# LoRa_Mini_Dev_v1_1.net
KiCad netlist of a schematic drawn in EAGLE
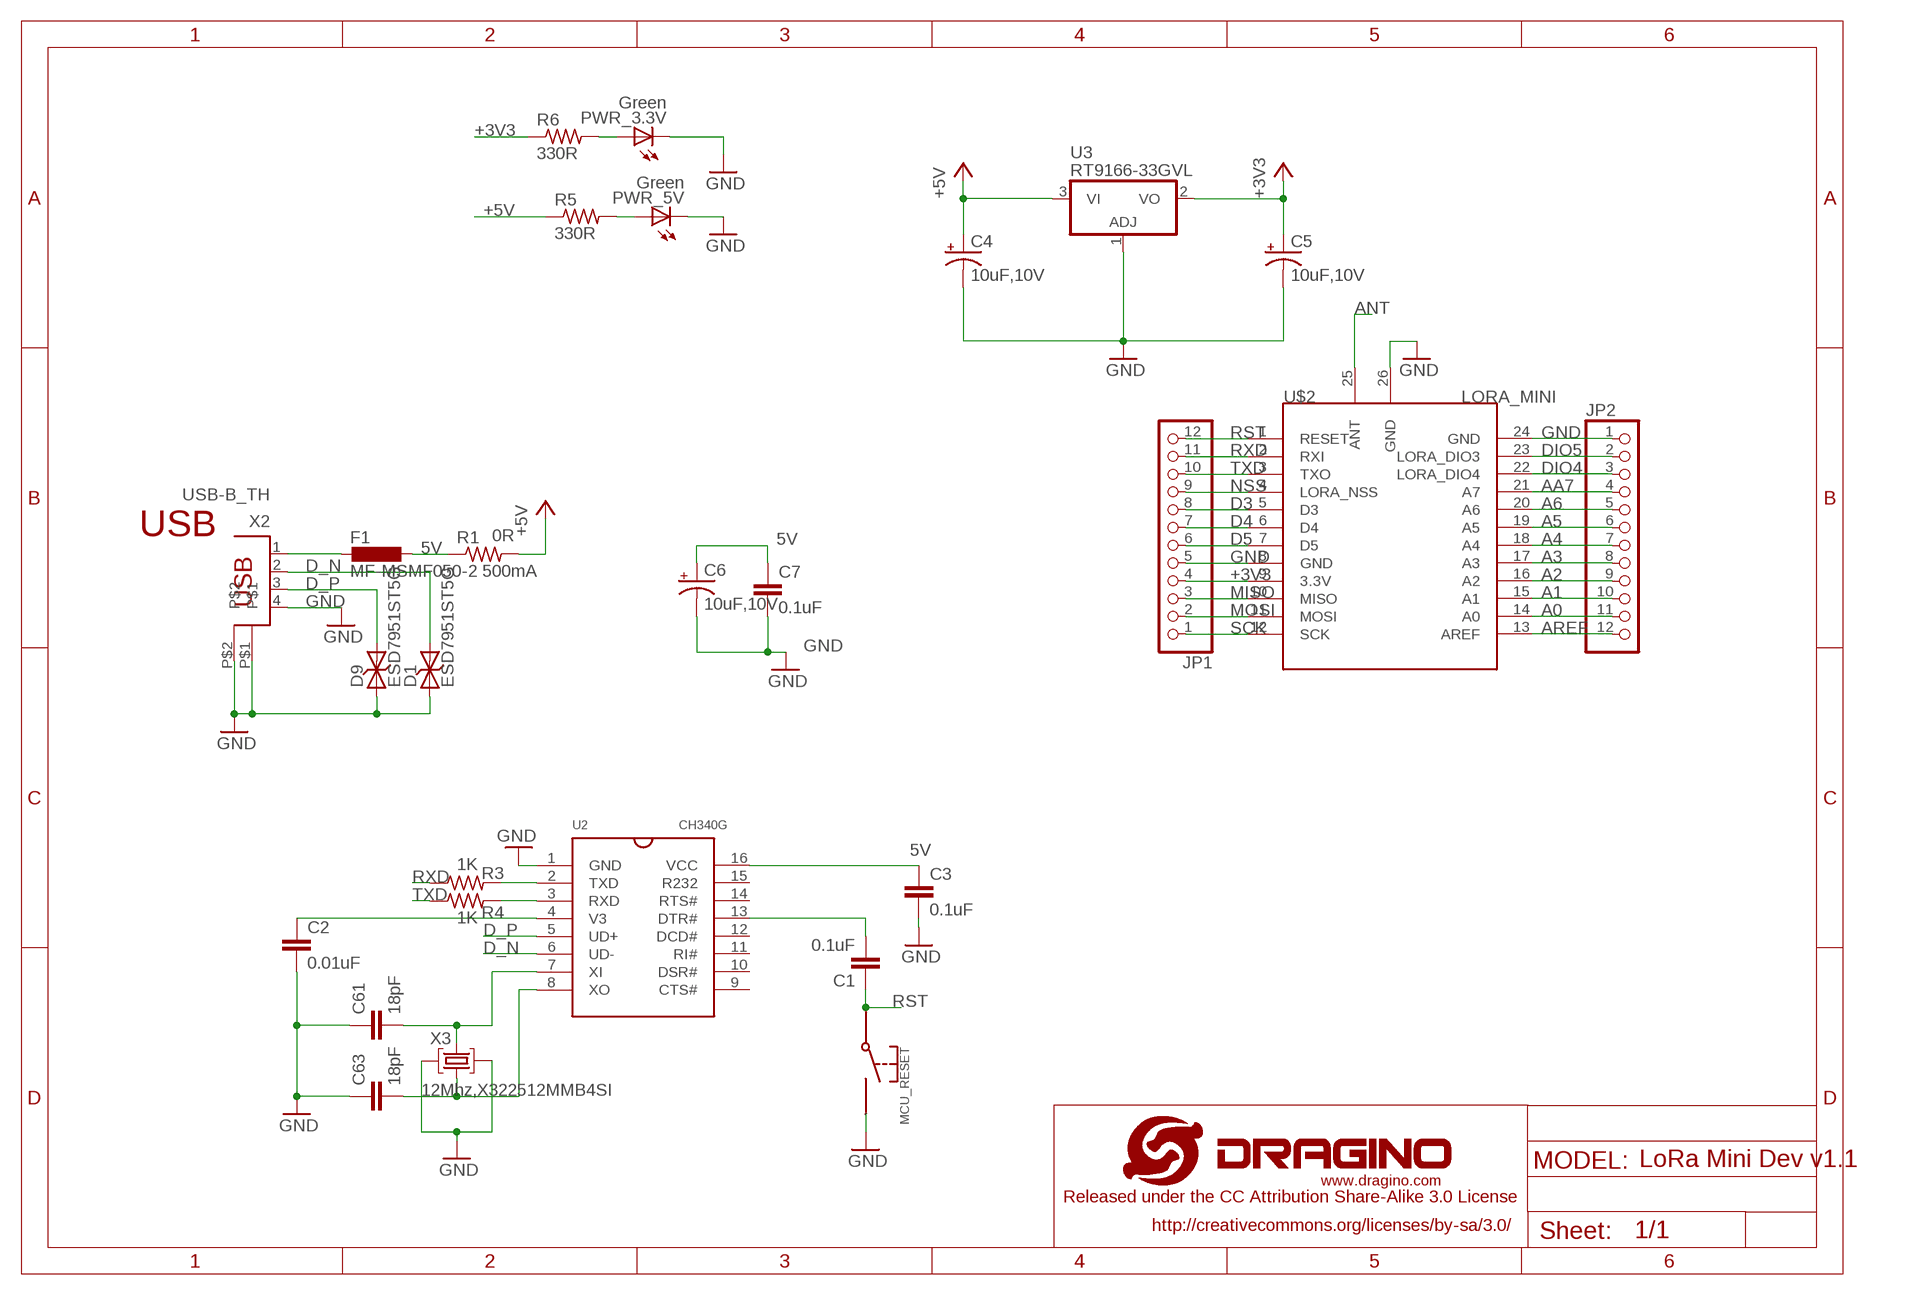
[diagram p0: schematic, sheet 1]

(export (version "E")
  (design (tool "Eeschema 10.0.6"))
  (components
    (comp (ref "C1")
      (value "0.1uF")
      (footprint "eagle-import:C0402")
      (libsource (lib "eagle-import") (part "C-EUC0402"))
    )
    (comp (ref "C2")
      (value "0.01uF")
      (footprint "eagle-import:C0402")
      (libsource (lib "eagle-import") (part "C-EUC0402"))
    )
    (comp (ref "C3")
      (value "0.1uF")
      (footprint "eagle-import:C0402")
      (libsource (lib "eagle-import") (part "C-EUC0402"))
    )
    (comp (ref "C4")
      (value "10uF,10V")
      (footprint "eagle-import:SMC_A")
      (libsource (lib "eagle-import") (part "CPOL-USSMCA"))
    )
    (comp (ref "C5")
      (value "10uF,10V")
      (footprint "eagle-import:SMC_A")
      (libsource (lib "eagle-import") (part "CPOL-USSMCA"))
    )
    (comp (ref "C6")
      (value "10uF,10V")
      (footprint "eagle-import:SMC_A")
      (libsource (lib "eagle-import") (part "CPOL-USSMCA"))
    )
    (comp (ref "C7")
      (value "0.1uF")
      (footprint "eagle-import:C0402")
      (libsource (lib "eagle-import") (part "C-EUC0402"))
    )
    (comp (ref "C61")
      (value "18pF")
      (footprint "eagle-import:C0402")
      (libsource (lib "eagle-import") (part "C-EUC0402"))
    )
    (comp (ref "C63")
      (value "18pF")
      (footprint "eagle-import:C0402")
      (libsource (lib "eagle-import") (part "C-EUC0402"))
    )
    (comp (ref "D1")
      (value "ESD7951ST5G")
      (footprint "eagle-import:SOD−923")
      (libsource (lib "eagle-import") (part "TVSSOD−923"))
    )
    (comp (ref "D9")
      (value "ESD7951ST5G")
      (footprint "eagle-import:SOD−923")
      (libsource (lib "eagle-import") (part "TVSSOD−923"))
    )
    (comp (ref "F1")
      (value "MF-MSMF050-2 500mA")
      (footprint "eagle-import:L1812")
      (libsource (lib "eagle-import") (part "L-EUL1812"))
    )
    (comp (ref "JP1")
      (value "PINHD-1X12")
      (footprint "eagle-import:1X12")
      (libsource (lib "eagle-import") (part "PINHD-1X12"))
    )
    (comp (ref "JP2")
      (value "PINHD-1X12")
      (footprint "eagle-import:1X12")
      (libsource (lib "eagle-import") (part "PINHD-1X12"))
    )
    (comp (ref "MCU_RESET")
      (value "SWITCH")
      (footprint "eagle-import:SWITCH_3X6X5MM")
      (libsource (lib "eagle-import") (part "SWITCH"))
    )
    (comp (ref "PWR_3.3V")
      (value "Green")
      (footprint "eagle-import:DRAGINO_CHIPLED_0603")
      (libsource (lib "eagle-import") (part "DRAGINO_LEDCHIPLED_0603"))
    )
    (comp (ref "PWR_5V")
      (value "Green")
      (footprint "eagle-import:DRAGINO_CHIPLED_0603")
      (libsource (lib "eagle-import") (part "DRAGINO_LEDCHIPLED_0603"))
    )
    (comp (ref "R1")
      (value "0R")
      (footprint "eagle-import:M0805")
      (libsource (lib "eagle-import") (part "R-US_M0805"))
    )
    (comp (ref "R3")
      (value "1K")
      (footprint "eagle-import:R0402")
      (libsource (lib "eagle-import") (part "R-US_R0402"))
    )
    (comp (ref "R4")
      (value "1K")
      (footprint "eagle-import:R0402")
      (libsource (lib "eagle-import") (part "R-US_R0402"))
    )
    (comp (ref "R5")
      (value "330R")
      (footprint "eagle-import:R0402")
      (libsource (lib "eagle-import") (part "R-US_R0402"))
    )
    (comp (ref "R6")
      (value "330R")
      (footprint "eagle-import:R0402")
      (libsource (lib "eagle-import") (part "R-US_R0402"))
    )
    (comp (ref "U$1")
      (value "LOGO-NEW")
      (footprint "eagle-import:LOGO-SILK-NEW")
      (libsource (lib "eagle-import") (part "LOGO-NEW"))
    )
    (comp (ref "U$2")
      (value "LORA_MINI")
      (footprint "eagle-import:LORA_MINI_PCB")
      (libsource (lib "eagle-import") (part "LORA_MINIB"))
    )
    (comp (ref "U2")
      (value "CH340G")
      (footprint "eagle-import:CH340G")
      (libsource (lib "eagle-import") (part "CH340G"))
    )
    (comp (ref "U3")
      (value "RT9166-33GVL")
      (footprint "eagle-import:SOT23")
      (libsource (lib "eagle-import") (part "RT9166/A"))
    )
    (comp (ref "X2")
      (value "USB-B_TH")
      (footprint "eagle-import:PN61729")
      (libsource (lib "eagle-import") (part "PN61729"))
    )
    (comp (ref "X3")
      (value "12Mhz,X322512MMB4SI")
      (footprint "eagle-import:SMARTPRJ_CRYSTAL-3.2-2.5")
      (libsource (lib "eagle-import") (part "CRYSTAL"))
    )
  )
  (nets
    (net (code "1") (name "+3V3") (class "Default")
      (node (ref "C5") (pin "+") (pinfunction "+_+") (pintype "passive"))
      (node (ref "JP1") (pin "4") (pinfunction "4_4") (pintype "passive"))
      (node (ref "R6") (pin "1") (pinfunction "1_1") (pintype "passive"))
      (node (ref "U$2") (pin "9") (pinfunction "3.3V_9") (pintype "bidirectional"))
      (node (ref "U3") (pin "2") (pinfunction "VO_2") (pintype "passive"))
    )
    (net (code "2") (name "+5V") (class "Default")
      (node (ref "C4") (pin "+") (pinfunction "+_+") (pintype "passive"))
      (node (ref "R1") (pin "2") (pinfunction "2_2") (pintype "passive"))
      (node (ref "R5") (pin "1") (pinfunction "1_1") (pintype "passive"))
      (node (ref "U3") (pin "3") (pinfunction "VI_3") (pintype "input"))
    )
    (net (code "3") (name "/5V") (class "Default")
      (node (ref "C3") (pin "1") (pinfunction "1_1") (pintype "passive"))
      (node (ref "C6") (pin "+") (pinfunction "+_+") (pintype "passive"))
      (node (ref "C7") (pin "1") (pinfunction "1_1") (pintype "passive"))
      (node (ref "F1") (pin "1") (pinfunction "1_1") (pintype "passive"))
      (node (ref "R1") (pin "1") (pinfunction "1_1") (pintype "passive"))
      (node (ref "U2") (pin "16") (pinfunction "VCC_16") (pintype "bidirectional"))
    )
    (net (code "4") (name "/A0") (class "Default")
      (node (ref "JP2") (pin "11") (pinfunction "11_11") (pintype "passive"))
      (node (ref "U$2") (pin "14") (pinfunction "A0_14") (pintype "bidirectional"))
    )
    (net (code "5") (name "/A1") (class "Default")
      (node (ref "JP2") (pin "10") (pinfunction "10_10") (pintype "passive"))
      (node (ref "U$2") (pin "15") (pinfunction "A1_15") (pintype "bidirectional"))
    )
    (net (code "6") (name "/A2") (class "Default")
      (node (ref "JP2") (pin "9") (pinfunction "9_9") (pintype "passive"))
      (node (ref "U$2") (pin "16") (pinfunction "A2_16") (pintype "bidirectional"))
    )
    (net (code "7") (name "/A3") (class "Default")
      (node (ref "JP2") (pin "8") (pinfunction "8_8") (pintype "passive"))
      (node (ref "U$2") (pin "17") (pinfunction "A3_17") (pintype "bidirectional"))
    )
    (net (code "8") (name "/A4") (class "Default")
      (node (ref "JP2") (pin "7") (pinfunction "7_7") (pintype "passive"))
      (node (ref "U$2") (pin "18") (pinfunction "A4_18") (pintype "bidirectional"))
    )
    (net (code "9") (name "/A5") (class "Default")
      (node (ref "JP2") (pin "6") (pinfunction "6_6") (pintype "passive"))
      (node (ref "U$2") (pin "19") (pinfunction "A5_19") (pintype "bidirectional"))
    )
    (net (code "10") (name "/A6") (class "Default")
      (node (ref "JP2") (pin "5") (pinfunction "5_5") (pintype "passive"))
      (node (ref "U$2") (pin "20") (pinfunction "A6_20") (pintype "bidirectional"))
    )
    (net (code "11") (name "/AA7") (class "Default")
      (node (ref "JP2") (pin "4") (pinfunction "4_4") (pintype "passive"))
      (node (ref "U$2") (pin "21") (pinfunction "A7_21") (pintype "bidirectional"))
    )
    (net (code "12") (name "/ANT") (class "Default")
      (node (ref "U$2") (pin "25") (pinfunction "ANT_25") (pintype "bidirectional"))
    )
    (net (code "13") (name "/AREF") (class "Default")
      (node (ref "JP2") (pin "12") (pinfunction "12_12") (pintype "passive"))
      (node (ref "U$2") (pin "13") (pinfunction "AREF_13") (pintype "bidirectional"))
    )
    (net (code "14") (name "/D3") (class "Default")
      (node (ref "JP1") (pin "8") (pinfunction "8_8") (pintype "passive"))
      (node (ref "U$2") (pin "5") (pinfunction "D3_5") (pintype "bidirectional"))
    )
    (net (code "15") (name "/D4") (class "Default")
      (node (ref "JP1") (pin "7") (pinfunction "7_7") (pintype "passive"))
      (node (ref "U$2") (pin "6") (pinfunction "D4_6") (pintype "bidirectional"))
    )
    (net (code "16") (name "/D5") (class "Default")
      (node (ref "JP1") (pin "6") (pinfunction "6_6") (pintype "passive"))
      (node (ref "U$2") (pin "7") (pinfunction "D5_7") (pintype "bidirectional"))
    )
    (net (code "17") (name "/DIO4") (class "Default")
      (node (ref "JP2") (pin "3") (pinfunction "3_3") (pintype "passive"))
      (node (ref "U$2") (pin "22") (pinfunction "LORA_DIO4_22") (pintype "bidirectional"))
    )
    (net (code "18") (name "/DIO5") (class "Default")
      (node (ref "JP2") (pin "2") (pinfunction "2_2") (pintype "passive"))
      (node (ref "U$2") (pin "23") (pinfunction "LORA_DIO3_23") (pintype "bidirectional"))
    )
    (net (code "19") (name "/D_N") (class "Default")
      (node (ref "D1") (pin "P$2") (pinfunction "2_P$2") (pintype "passive"))
      (node (ref "U2") (pin "6") (pinfunction "UD-_6") (pintype "bidirectional"))
      (node (ref "X2") (pin "2") (pinfunction "2_2") (pintype "bidirectional"))
    )
    (net (code "20") (name "/D_P") (class "Default")
      (node (ref "D9") (pin "P$2") (pinfunction "2_P$2") (pintype "passive"))
      (node (ref "U2") (pin "5") (pinfunction "UD+_5") (pintype "bidirectional"))
      (node (ref "X2") (pin "3") (pinfunction "3_3") (pintype "bidirectional"))
    )
    (net (code "21") (name "/MISO") (class "Default")
      (node (ref "JP1") (pin "3") (pinfunction "3_3") (pintype "passive"))
      (node (ref "U$2") (pin "10") (pinfunction "MISO_10") (pintype "bidirectional"))
    )
    (net (code "22") (name "/MOSI") (class "Default")
      (node (ref "JP1") (pin "2") (pinfunction "2_2") (pintype "passive"))
      (node (ref "U$2") (pin "11") (pinfunction "MOSI_11") (pintype "bidirectional"))
    )
    (net (code "23") (name "/NSS") (class "Default")
      (node (ref "JP1") (pin "9") (pinfunction "9_9") (pintype "passive"))
      (node (ref "U$2") (pin "4") (pinfunction "LORA_NSS_4") (pintype "bidirectional"))
    )
    (net (code "24") (name "/RST") (class "Default")
      (node (ref "C1") (pin "1") (pinfunction "1_1") (pintype "passive"))
      (node (ref "JP1") (pin "12") (pinfunction "12_12") (pintype "passive"))
      (node (ref "MCU_RESET") (pin "P$1") (pinfunction "P$1_P$1") (pintype "bidirectional"))
      (node (ref "U$2") (pin "1") (pinfunction "RESET_1") (pintype "bidirectional"))
    )
    (net (code "25") (name "/RXD") (class "Default")
      (node (ref "JP1") (pin "11") (pinfunction "11_11") (pintype "passive"))
      (node (ref "R3") (pin "1") (pinfunction "1_1") (pintype "passive"))
      (node (ref "U$2") (pin "2") (pinfunction "RXI_2") (pintype "bidirectional"))
    )
    (net (code "26") (name "/SCK") (class "Default")
      (node (ref "JP1") (pin "1") (pinfunction "1_1") (pintype "passive"))
      (node (ref "U$2") (pin "12") (pinfunction "SCK_12") (pintype "bidirectional"))
    )
    (net (code "27") (name "/TXD") (class "Default")
      (node (ref "JP1") (pin "10") (pinfunction "10_10") (pintype "passive"))
      (node (ref "R4") (pin "1") (pinfunction "1_1") (pintype "passive"))
      (node (ref "U$2") (pin "3") (pinfunction "TXO_3") (pintype "bidirectional"))
    )
    (net (code "28") (name "GND") (class "Default")
      (node (ref "C2") (pin "2") (pinfunction "2_2") (pintype "passive"))
      (node (ref "C3") (pin "2") (pinfunction "2_2") (pintype "passive"))
      (node (ref "C4") (pin "-") (pinfunction "-_-") (pintype "passive"))
      (node (ref "C5") (pin "-") (pinfunction "-_-") (pintype "passive"))
      (node (ref "C6") (pin "-") (pinfunction "-_-") (pintype "passive"))
      (node (ref "C61") (pin "1") (pinfunction "1_1") (pintype "passive"))
      (node (ref "C63") (pin "1") (pinfunction "1_1") (pintype "passive"))
      (node (ref "C7") (pin "2") (pinfunction "2_2") (pintype "passive"))
      (node (ref "D1") (pin "P$1") (pinfunction "1_P$1") (pintype "passive"))
      (node (ref "D9") (pin "P$1") (pinfunction "1_P$1") (pintype "passive"))
      (node (ref "JP1") (pin "5") (pinfunction "5_5") (pintype "passive"))
      (node (ref "JP2") (pin "1") (pinfunction "1_1") (pintype "passive"))
      (node (ref "MCU_RESET") (pin "P$2") (pinfunction "P$2_P$2") (pintype "bidirectional"))
      (node (ref "PWR_3.3V") (pin "C") (pinfunction "C_C") (pintype "passive"))
      (node (ref "PWR_5V") (pin "C") (pinfunction "C_C") (pintype "passive"))
      (node (ref "U$2") (pin "24") (pinfunction "GND_24") (pintype "bidirectional"))
      (node (ref "U$2") (pin "26") (pinfunction "GND_26") (pintype "bidirectional"))
      (node (ref "U$2") (pin "8") (pinfunction "GND_8") (pintype "bidirectional"))
      (node (ref "U2") (pin "1") (pinfunction "GND_1") (pintype "bidirectional"))
      (node (ref "U3") (pin "1") (pinfunction "ADJ_1") (pintype "input"))
      (node (ref "X2") (pin "4") (pinfunction "4_4") (pintype "bidirectional"))
      (node (ref "X2") (pin "P$1") (pinfunction "P$1_P$1") (pintype "bidirectional"))
      (node (ref "X2") (pin "P$2") (pinfunction "P$2_P$2") (pintype "bidirectional"))
      (node (ref "X3") (pin "2") (pinfunction "GND_2") (pintype "passive"))
      (node (ref "X3") (pin "4") (pinfunction "GND_4") (pintype "passive"))
    )
    (net (code "29") (name "Net-(F1-Pad2)") (class "Default")
      (node (ref "F1") (pin "2") (pinfunction "2_2") (pintype "passive"))
      (node (ref "X2") (pin "1") (pinfunction "1_1") (pintype "bidirectional"))
    )
    (net (code "30") (name "Net-(PWR_3.3V-PadA)") (class "Default")
      (node (ref "PWR_3.3V") (pin "A") (pinfunction "A_A") (pintype "passive"))
      (node (ref "R6") (pin "2") (pinfunction "2_2") (pintype "passive"))
    )
    (net (code "31") (name "Net-(PWR_5V-PadA)") (class "Default")
      (node (ref "PWR_5V") (pin "A") (pinfunction "A_A") (pintype "passive"))
      (node (ref "R5") (pin "2") (pinfunction "2_2") (pintype "passive"))
    )
    (net (code "32") (name "Net-(U2-DTR#)") (class "Default")
      (node (ref "C1") (pin "2") (pinfunction "2_2") (pintype "passive"))
      (node (ref "U2") (pin "13") (pinfunction "DTR#_13") (pintype "bidirectional"))
    )
    (net (code "33") (name "Net-(U2-RXD)") (class "Default")
      (node (ref "R4") (pin "2") (pinfunction "2_2") (pintype "passive"))
      (node (ref "U2") (pin "3") (pinfunction "RXD_3") (pintype "bidirectional"))
    )
    (net (code "34") (name "Net-(U2-TXD)") (class "Default")
      (node (ref "R3") (pin "2") (pinfunction "2_2") (pintype "passive"))
      (node (ref "U2") (pin "2") (pinfunction "TXD_2") (pintype "bidirectional"))
    )
    (net (code "35") (name "Net-(U2-V3)") (class "Default")
      (node (ref "C2") (pin "1") (pinfunction "1_1") (pintype "passive"))
      (node (ref "U2") (pin "4") (pinfunction "V3_4") (pintype "bidirectional"))
    )
    (net (code "36") (name "Net-(U2-XI)") (class "Default")
      (node (ref "C61") (pin "2") (pinfunction "2_2") (pintype "passive"))
      (node (ref "U2") (pin "7") (pinfunction "XI_7") (pintype "bidirectional"))
      (node (ref "X3") (pin "3") (pinfunction "C2_3") (pintype "passive"))
    )
    (net (code "37") (name "Net-(U2-XO)") (class "Default")
      (node (ref "C63") (pin "2") (pinfunction "2_2") (pintype "passive"))
      (node (ref "U2") (pin "8") (pinfunction "XO_8") (pintype "bidirectional"))
      (node (ref "X3") (pin "1") (pinfunction "C1_1") (pintype "passive"))
    )
    (net (code "38") (name "unconnected-(U2-CTS#-Pad9)") (class "Default")
      (node (ref "U2") (pin "9") (pinfunction "CTS#_9") (pintype "bidirectional"))
    )
    (net (code "39") (name "unconnected-(U2-DCD#-Pad12)") (class "Default")
      (node (ref "U2") (pin "12") (pinfunction "DCD#_12") (pintype "bidirectional"))
    )
    (net (code "40") (name "unconnected-(U2-DSR#-Pad10)") (class "Default")
      (node (ref "U2") (pin "10") (pinfunction "DSR#_10") (pintype "bidirectional"))
    )
    (net (code "41") (name "unconnected-(U2-R232-Pad15)") (class "Default")
      (node (ref "U2") (pin "15") (pinfunction "R232_15") (pintype "bidirectional"))
    )
    (net (code "42") (name "unconnected-(U2-RI#-Pad11)") (class "Default")
      (node (ref "U2") (pin "11") (pinfunction "RI#_11") (pintype "bidirectional"))
    )
    (net (code "43") (name "unconnected-(U2-RTS#-Pad14)") (class "Default")
      (node (ref "U2") (pin "14") (pinfunction "RTS#_14") (pintype "bidirectional"))
    )
  )
)
